# SuCOELora.net
KiCad netlist of a schematic drawn in Altium Designer
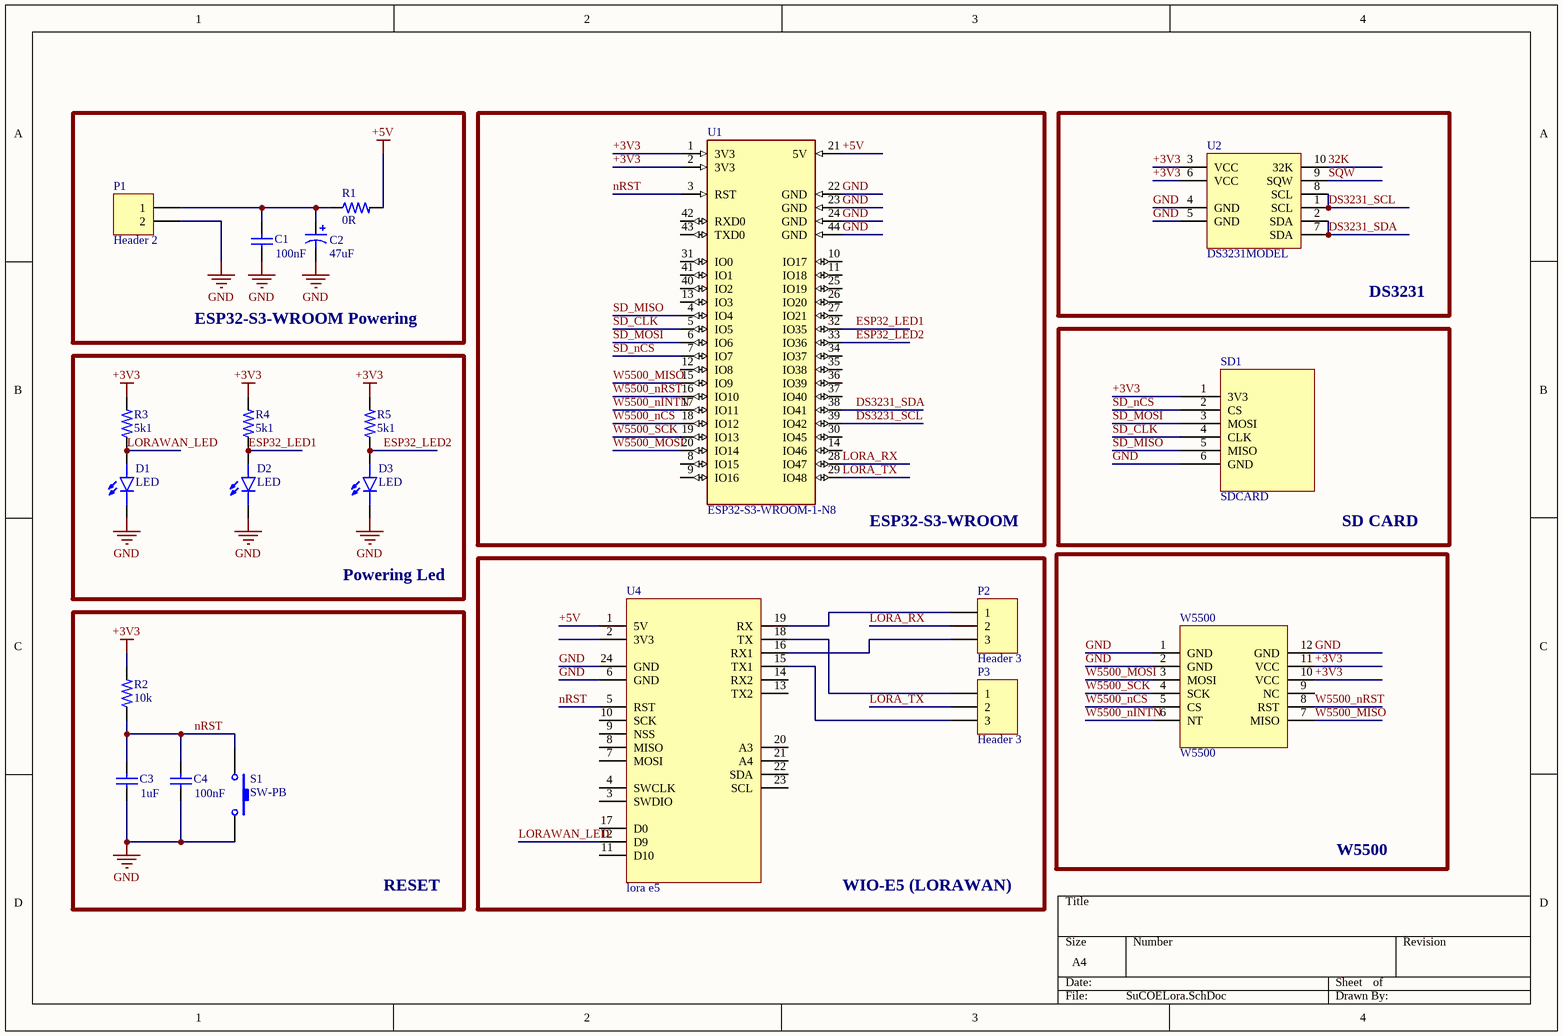
[diagram p0: SuCOELora.SchDoc]

(export (version "E")
  (design (tool "Eeschema 10.0.6"))
  (components
    (comp (ref "C1")
      (value "100nF")
      (footprint "CC0805")
      (description "Capacitor")
      (fields (field (name "Comment") "0805-50V-100nF±1%") (field (name "PUBLISHER") "Altium Limited"))
      (libsource (lib "Miscellaneous Devices") (part "Cap"))
    )
    (comp (ref "C2")
      (value "47uF")
      (footprint "SMD-EC-F4")
      (description "Polarized Capacitor (Radial)")
      (fields (field (name "Comment") "SMD-25V-47uF") (field (name "PUBLISHER") "Altium Limited"))
      (libsource (lib "Miscellaneous Devices") (part "Cap Pol1"))
    )
    (comp (ref "C3")
      (value "1uF")
      (footprint "CC0805")
      (description "Capacitor")
      (fields (field (name "Comment") "0805-50V-1uF±1%") (field (name "PUBLISHER") "Altium Limited"))
      (libsource (lib "Miscellaneous Devices") (part "Cap"))
    )
    (comp (ref "C4")
      (value "100nF")
      (footprint "CC0805")
      (description "Capacitor")
      (fields (field (name "Comment") "0805-50V-100nF±1%") (field (name "PUBLISHER") "Altium Limited"))
      (libsource (lib "Miscellaneous Devices") (part "Cap"))
    )
    (comp (ref "D1")
      (value "LED")
      (footprint "LED-R3")
      (description "LED Uni-Color Red 2-Pin Chip 0805 T/R")
      (fields (field (name "MP") "597-3305-607F"))
      (libsource (lib "Integrated_Library") (part "597-3305-607F"))
    )
    (comp (ref "D2")
      (value "LED")
      (footprint "LED-R3")
      (description "LED Uni-Color Red 2-Pin Chip 0805 T/R")
      (fields (field (name "MP") "597-3305-607F"))
      (libsource (lib "Integrated_Library") (part "597-3305-607F"))
    )
    (comp (ref "D3")
      (value "LED")
      (footprint "LED-R3")
      (description "LED Uni-Color Red 2-Pin Chip 0805 T/R")
      (fields (field (name "MP") "597-3305-607F"))
      (libsource (lib "Integrated_Library") (part "597-3305-607F"))
    )
    (comp (ref "P1")
      (value "Header 2")
      (footprint "2EDJKM3.81-2P")
      (description "Header, 2-Pin")
      (fields (field (name "PUBLISHER") "Altium Limited"))
      (libsource (lib "Miscellaneous Connectors") (part "Header 2"))
    )
    (comp (ref "P2")
      (value "Header 3")
      (footprint "HDR1X3")
      (description "Header, 3-Pin")
      (fields (field (name "PUBLISHER") "Altium Limited"))
      (libsource (lib "Miscellaneous Connectors") (part "Header 3"))
    )
    (comp (ref "P3")
      (value "Header 3")
      (footprint "HDR1X3")
      (description "Header, 3-Pin")
      (fields (field (name "PUBLISHER") "Altium Limited"))
      (libsource (lib "Miscellaneous Connectors") (part "Header 3"))
    )
    (comp (ref "R1")
      (value "0R")
      (footprint "0805")
      (description "SMD Chip Resistor, Jumper, 0 ohm, 100 mW, 0402 [1005 Metric], Thick Film, General Purpose")
      (fields
        (field (name "MANUFACTURER") "Panasonic")
        (field (name "MANUFACTURER PART NUMBER") "ERJ-2GE0R00X")
      )
      (libsource (lib "Integrated_Library") (part "0402 SMD Resistor"))
    )
    (comp (ref "R2")
      (value "10k")
      (footprint "0805")
      (description "Res Thick Film 0402 10K Ohm 5% 0.125W(1/8W) ±200ppm/C Pad SMD T/R")
      (fields
        (field (name "MANUFACTURER") "Yageo")
        (field (name "MANUFACTURER PART NUMBER") "RC0402JR-7W10KL")
      )
      (libsource (lib "Integrated_Library") (part "0402 SMD Resistor"))
    )
    (comp (ref "R3")
      (value "5k1")
      (footprint "0805")
      (description "General Purpose Chip Resistor Thick Film 0402 5.1kOhm 1% Paper T/R")
      (fields
        (field (name "MANUFACTURER") "Yageo")
        (field (name "MANUFACTURER PART NUMBER") "RC0402FR-7W5K1L")
      )
      (libsource (lib "Integrated_Library") (part "0402 SMD Resistor"))
    )
    (comp (ref "R4")
      (value "5k1")
      (footprint "0805")
      (description "General Purpose Chip Resistor Thick Film 0402 5.1kOhm 1% Paper T/R")
      (fields
        (field (name "MANUFACTURER") "Yageo")
        (field (name "MANUFACTURER PART NUMBER") "RC0402FR-7W5K1L")
      )
      (libsource (lib "Integrated_Library") (part "0402 SMD Resistor"))
    )
    (comp (ref "R5")
      (value "5k1")
      (footprint "0805")
      (description "General Purpose Chip Resistor Thick Film 0402 5.1kOhm 1% Paper T/R")
      (fields
        (field (name "MANUFACTURER") "Yageo")
        (field (name "MANUFACTURER PART NUMBER") "RC0402FR-7W5K1L")
      )
      (libsource (lib "Integrated_Library") (part "0402 SMD Resistor"))
    )
    (comp (ref "S1")
      (value "SW-PB")
      (footprint "KEY-4P")
      (description "Switch")
      (fields (field (name "PUBLISHER") "Altium Limited"))
      (libsource (lib "Miscellaneous Devices") (part "SW-PB"))
    )
    (comp (ref "SD1") (value "SDCARD") (footprint "SDCARD") (libsource (lib "PCB_Project") (part "SDCARD")))
    (comp (ref "U1")
      (value "ESP32-S3-WROOM-1-N8")
      (footprint "ESP32-S3")
      (fields (field (name "MF") "{'manufacturer': u'Espressif Systems'}"))
      (libsource (lib "PCB_Project") (part "ESP32-S3-WROOM-1-N8"))
    )
    (comp (ref "U2")
      (value "DS3231MODEL")
      (footprint "DS3231")
      (libsource (lib "PCB_Project") (part "DS3231MODEL"))
    )
    (comp (ref "U4")
      (value "lora e5")
      (footprint "USB2.0-TYPE-C")
      (libsource (lib "SuCOELora") (part "lora e5"))
    )
    (comp (ref "W5500") (value "W5500") (footprint "W5500") (libsource (lib "PCB_Project") (part "W5500")))
  )
  (nets
    (net (code "1") (name "+3V3") (class "Default")
      (node (ref "R2") (pin "2") (pinfunction "2_2") (pintype "passive"))
      (node (ref "R3") (pin "2") (pinfunction "2_2") (pintype "passive"))
      (node (ref "R4") (pin "2") (pinfunction "2_2") (pintype "passive"))
      (node (ref "R5") (pin "2") (pinfunction "2_2") (pintype "passive"))
      (node (ref "SD1") (pin "1") (pinfunction "3V3_1") (pintype "passive"))
      (node (ref "U1") (pin "1") (pinfunction "3V3_1") (pintype "input"))
      (node (ref "U1") (pin "2") (pinfunction "3V3_2") (pintype "input"))
      (node (ref "U2") (pin "3") (pinfunction "VCC_3") (pintype "passive"))
      (node (ref "U2") (pin "6") (pinfunction "VCC_6") (pintype "passive"))
      (node (ref "W5500") (pin "10") (pinfunction "VCC_10") (pintype "passive"))
      (node (ref "W5500") (pin "11") (pinfunction "VCC_11") (pintype "passive"))
    )
    (net (code "2") (name "+5V") (class "Default")
      (node (ref "R1") (pin "2") (pinfunction "2_2") (pintype "passive"))
      (node (ref "U1") (pin "21") (pinfunction "5V_21") (pintype "input"))
      (node (ref "U4") (pin "1") (pinfunction "5V_1") (pintype "passive"))
    )
    (net (code "3") (name "/32K") (class "Default")
      (node (ref "U2") (pin "10") (pinfunction "32K_10") (pintype "passive"))
    )
    (net (code "4") (name "/DS3231_SCL") (class "Default")
      (node (ref "U1") (pin "39") (pinfunction "IO42_39") (pintype "bidirectional"))
      (node (ref "U2") (pin "1") (pinfunction "SCL_1") (pintype "passive"))
      (node (ref "U2") (pin "8") (pinfunction "SCL_8") (pintype "passive"))
    )
    (net (code "5") (name "/DS3231_SDA") (class "Default")
      (node (ref "U1") (pin "38") (pinfunction "IO41_38") (pintype "bidirectional"))
      (node (ref "U2") (pin "2") (pinfunction "SDA_2") (pintype "passive"))
      (node (ref "U2") (pin "7") (pinfunction "SDA_7") (pintype "passive"))
    )
    (net (code "6") (name "/ESP32_LED1") (class "Default")
      (node (ref "D2") (pin "1") (pinfunction "A_1") (pintype "passive"))
      (node (ref "R4") (pin "1") (pinfunction "1_1") (pintype "passive"))
      (node (ref "U1") (pin "32") (pinfunction "IO35_32") (pintype "bidirectional"))
    )
    (net (code "7") (name "/ESP32_LED2") (class "Default")
      (node (ref "D3") (pin "1") (pinfunction "A_1") (pintype "passive"))
      (node (ref "R5") (pin "1") (pinfunction "1_1") (pintype "passive"))
      (node (ref "U1") (pin "33") (pinfunction "IO36_33") (pintype "bidirectional"))
    )
    (net (code "8") (name "/LORAWAN_LED") (class "Default")
      (node (ref "D1") (pin "1") (pinfunction "A_1") (pintype "passive"))
      (node (ref "R3") (pin "1") (pinfunction "1_1") (pintype "passive"))
      (node (ref "U4") (pin "12") (pinfunction "D9_12") (pintype "passive"))
    )
    (net (code "9") (name "/LORA_RX") (class "Default")
      (node (ref "P2") (pin "2") (pinfunction "2_2") (pintype "passive"))
      (node (ref "U1") (pin "28") (pinfunction "IO47_28") (pintype "bidirectional"))
    )
    (net (code "10") (name "/LORA_TX") (class "Default")
      (node (ref "P3") (pin "2") (pinfunction "2_2") (pintype "passive"))
      (node (ref "U1") (pin "29") (pinfunction "IO48_29") (pintype "bidirectional"))
    )
    (net (code "11") (name "/SD_CLK") (class "Default")
      (node (ref "SD1") (pin "4") (pinfunction "CLK_4") (pintype "passive"))
      (node (ref "U1") (pin "5") (pinfunction "IO5_5") (pintype "bidirectional"))
    )
    (net (code "12") (name "/SD_MISO") (class "Default")
      (node (ref "SD1") (pin "5") (pinfunction "MISO_5") (pintype "passive"))
      (node (ref "U1") (pin "4") (pinfunction "IO4_4") (pintype "bidirectional"))
    )
    (net (code "13") (name "/SD_MOSI") (class "Default")
      (node (ref "SD1") (pin "3") (pinfunction "MOSI_3") (pintype "passive"))
      (node (ref "U1") (pin "6") (pinfunction "IO6_6") (pintype "bidirectional"))
    )
    (net (code "14") (name "/SD_nCS") (class "Default")
      (node (ref "SD1") (pin "2") (pinfunction "CS_2") (pintype "passive"))
      (node (ref "U1") (pin "7") (pinfunction "IO7_7") (pintype "bidirectional"))
    )
    (net (code "15") (name "/SQW") (class "Default")
      (node (ref "U2") (pin "9") (pinfunction "SQW_9") (pintype "passive"))
    )
    (net (code "16") (name "/W5500_MISO") (class "Default")
      (node (ref "U1") (pin "15") (pinfunction "IO9_15") (pintype "bidirectional"))
      (node (ref "W5500") (pin "7") (pinfunction "MISO_7") (pintype "passive"))
    )
    (net (code "17") (name "/W5500_MOSI") (class "Default")
      (node (ref "U1") (pin "20") (pinfunction "IO14_20") (pintype "bidirectional"))
      (node (ref "W5500") (pin "3") (pinfunction "MOSI_3") (pintype "passive"))
    )
    (net (code "18") (name "/W5500_SCK") (class "Default")
      (node (ref "U1") (pin "19") (pinfunction "IO13_19") (pintype "bidirectional"))
      (node (ref "W5500") (pin "4") (pinfunction "SCK_4") (pintype "passive"))
    )
    (net (code "19") (name "/W5500_nCS") (class "Default")
      (node (ref "U1") (pin "18") (pinfunction "IO12_18") (pintype "bidirectional"))
      (node (ref "W5500") (pin "5") (pinfunction "CS_5") (pintype "passive"))
    )
    (net (code "20") (name "/W5500_nINTN") (class "Default")
      (node (ref "U1") (pin "17") (pinfunction "IO11_17") (pintype "bidirectional"))
      (node (ref "W5500") (pin "6") (pinfunction "NT_6") (pintype "passive"))
    )
    (net (code "21") (name "/W5500_nRST") (class "Default")
      (node (ref "U1") (pin "16") (pinfunction "IO10_16") (pintype "bidirectional"))
      (node (ref "W5500") (pin "8") (pinfunction "RST_8") (pintype "passive"))
    )
    (net (code "22") (name "/nRST") (class "Default")
      (node (ref "C3") (pin "2") (pinfunction "2_2") (pintype "passive"))
      (node (ref "C4") (pin "2") (pinfunction "2_2") (pintype "passive"))
      (node (ref "R2") (pin "1") (pinfunction "1_1") (pintype "passive"))
      (node (ref "S1") (pin "1") (pinfunction "1_1") (pintype "passive"))
      (node (ref "U1") (pin "3") (pinfunction "RST_3") (pintype "input"))
      (node (ref "U4") (pin "5") (pinfunction "RST_5") (pintype "passive"))
    )
    (net (code "23") (name "GND") (class "Default")
      (node (ref "C1") (pin "1") (pinfunction "1_1") (pintype "passive"))
      (node (ref "C2") (pin "2") (pinfunction "2_2") (pintype "passive"))
      (node (ref "C3") (pin "1") (pinfunction "1_1") (pintype "passive"))
      (node (ref "C4") (pin "1") (pinfunction "1_1") (pintype "passive"))
      (node (ref "D1") (pin "2") (pinfunction "C_2") (pintype "passive"))
      (node (ref "D2") (pin "2") (pinfunction "C_2") (pintype "passive"))
      (node (ref "D3") (pin "2") (pinfunction "C_2") (pintype "passive"))
      (node (ref "P1") (pin "2") (pinfunction "2_2") (pintype "passive"))
      (node (ref "S1") (pin "2") (pinfunction "2_2") (pintype "passive"))
      (node (ref "SD1") (pin "6") (pinfunction "GND_6") (pintype "passive"))
      (node (ref "U1") (pin "22") (pinfunction "GND_22") (pintype "input"))
      (node (ref "U1") (pin "23") (pinfunction "GND_23") (pintype "input"))
      (node (ref "U1") (pin "24") (pinfunction "GND_24") (pintype "input"))
      (node (ref "U1") (pin "44") (pinfunction "GND_44") (pintype "input"))
      (node (ref "U2") (pin "4") (pinfunction "GND_4") (pintype "passive"))
      (node (ref "U2") (pin "5") (pinfunction "GND_5") (pintype "passive"))
      (node (ref "U4") (pin "24") (pinfunction "GND_24") (pintype "passive"))
      (node (ref "U4") (pin "6") (pinfunction "GND_6") (pintype "passive"))
      (node (ref "W5500") (pin "1") (pinfunction "GND_1") (pintype "passive"))
      (node (ref "W5500") (pin "12") (pinfunction "GND_12") (pintype "passive"))
      (node (ref "W5500") (pin "2") (pinfunction "GND_2") (pintype "passive"))
    )
    (net (code "24") (name "Net-(C1-Pad2)") (class "Default")
      (node (ref "C1") (pin "2") (pinfunction "2_2") (pintype "passive"))
      (node (ref "C2") (pin "1") (pinfunction "1_1") (pintype "passive"))
      (node (ref "P1") (pin "1") (pinfunction "1_1") (pintype "passive"))
      (node (ref "R1") (pin "1") (pinfunction "1_1") (pintype "passive"))
    )
    (net (code "25") (name "Net-(U4-RX)") (class "Default")
      (node (ref "P2") (pin "1") (pinfunction "1_1") (pintype "passive"))
      (node (ref "U4") (pin "19") (pinfunction "RX_19") (pintype "passive"))
    )
    (net (code "26") (name "Net-(U4-RX1)") (class "Default")
      (node (ref "P2") (pin "3") (pinfunction "3_3") (pintype "passive"))
      (node (ref "U4") (pin "16") (pinfunction "RX1_16") (pintype "passive"))
    )
    (net (code "27") (name "Net-(U4-TX)") (class "Default")
      (node (ref "P3") (pin "1") (pinfunction "1_1") (pintype "passive"))
      (node (ref "U4") (pin "18") (pinfunction "TX_18") (pintype "passive"))
    )
    (net (code "28") (name "Net-(U4-TX1)") (class "Default")
      (node (ref "P3") (pin "3") (pinfunction "3_3") (pintype "passive"))
      (node (ref "U4") (pin "15") (pinfunction "TX1_15") (pintype "passive"))
    )
    (net (code "29") (name "unconnected-(U1-IO0-Pad31)") (class "Default")
      (node (ref "U1") (pin "31") (pinfunction "IO0_31") (pintype "bidirectional"))
    )
    (net (code "30") (name "unconnected-(U1-IO1-Pad41)") (class "Default")
      (node (ref "U1") (pin "41") (pinfunction "IO1_41") (pintype "bidirectional"))
    )
    (net (code "31") (name "unconnected-(U1-IO2-Pad40)") (class "Default")
      (node (ref "U1") (pin "40") (pinfunction "IO2_40") (pintype "bidirectional"))
    )
    (net (code "32") (name "unconnected-(U1-IO3-Pad13)") (class "Default")
      (node (ref "U1") (pin "13") (pinfunction "IO3_13") (pintype "bidirectional"))
    )
    (net (code "33") (name "unconnected-(U1-IO8-Pad12)") (class "Default")
      (node (ref "U1") (pin "12") (pinfunction "IO8_12") (pintype "bidirectional"))
    )
    (net (code "34") (name "unconnected-(U1-IO15-Pad8)") (class "Default")
      (node (ref "U1") (pin "8") (pinfunction "IO15_8") (pintype "bidirectional"))
    )
    (net (code "35") (name "unconnected-(U1-IO16-Pad9)") (class "Default")
      (node (ref "U1") (pin "9") (pinfunction "IO16_9") (pintype "bidirectional"))
    )
    (net (code "36") (name "unconnected-(U1-IO17-Pad10)") (class "Default")
      (node (ref "U1") (pin "10") (pinfunction "IO17_10") (pintype "bidirectional"))
    )
    (net (code "37") (name "unconnected-(U1-IO18-Pad11)") (class "Default")
      (node (ref "U1") (pin "11") (pinfunction "IO18_11") (pintype "bidirectional"))
    )
    (net (code "38") (name "unconnected-(U1-IO19-Pad25)") (class "Default")
      (node (ref "U1") (pin "25") (pinfunction "IO19_25") (pintype "bidirectional"))
    )
    (net (code "39") (name "unconnected-(U1-IO20-Pad26)") (class "Default")
      (node (ref "U1") (pin "26") (pinfunction "IO20_26") (pintype "bidirectional"))
    )
    (net (code "40") (name "unconnected-(U1-IO21-Pad27)") (class "Default")
      (node (ref "U1") (pin "27") (pinfunction "IO21_27") (pintype "bidirectional"))
    )
    (net (code "41") (name "unconnected-(U1-IO37-Pad34)") (class "Default")
      (node (ref "U1") (pin "34") (pinfunction "IO37_34") (pintype "bidirectional"))
    )
    (net (code "42") (name "unconnected-(U1-IO38-Pad35)") (class "Default")
      (node (ref "U1") (pin "35") (pinfunction "IO38_35") (pintype "bidirectional"))
    )
    (net (code "43") (name "unconnected-(U1-IO39-Pad36)") (class "Default")
      (node (ref "U1") (pin "36") (pinfunction "IO39_36") (pintype "bidirectional"))
    )
    (net (code "44") (name "unconnected-(U1-IO40-Pad37)") (class "Default")
      (node (ref "U1") (pin "37") (pinfunction "IO40_37") (pintype "bidirectional"))
    )
    (net (code "45") (name "unconnected-(U1-IO45-Pad30)") (class "Default")
      (node (ref "U1") (pin "30") (pinfunction "IO45_30") (pintype "bidirectional"))
    )
    (net (code "46") (name "unconnected-(U1-IO46-Pad14)") (class "Default")
      (node (ref "U1") (pin "14") (pinfunction "IO46_14") (pintype "bidirectional"))
    )
    (net (code "47") (name "unconnected-(U1-RXD0-Pad42)") (class "Default")
      (node (ref "U1") (pin "42") (pinfunction "RXD0_42") (pintype "bidirectional"))
    )
    (net (code "48") (name "unconnected-(U1-TXD0-Pad43)") (class "Default")
      (node (ref "U1") (pin "43") (pinfunction "TXD0_43") (pintype "bidirectional"))
    )
    (net (code "49") (name "unconnected-(U4-3V3-Pad2)") (class "Default")
      (node (ref "U4") (pin "2") (pinfunction "3V3_2") (pintype "passive"))
    )
    (net (code "50") (name "unconnected-(U4-A3-Pad20)") (class "Default")
      (node (ref "U4") (pin "20") (pinfunction "A3_20") (pintype "passive"))
    )
    (net (code "51") (name "unconnected-(U4-A4-Pad21)") (class "Default")
      (node (ref "U4") (pin "21") (pinfunction "A4_21") (pintype "passive"))
    )
    (net (code "52") (name "unconnected-(U4-D0-Pad17)") (class "Default")
      (node (ref "U4") (pin "17") (pinfunction "D0_17") (pintype "passive"))
    )
    (net (code "53") (name "unconnected-(U4-D10-Pad11)") (class "Default")
      (node (ref "U4") (pin "11") (pinfunction "D10_11") (pintype "passive"))
    )
    (net (code "54") (name "unconnected-(U4-MISO-Pad8)") (class "Default")
      (node (ref "U4") (pin "8") (pinfunction "MISO_8") (pintype "passive"))
    )
    (net (code "55") (name "unconnected-(U4-MOSI-Pad7)") (class "Default")
      (node (ref "U4") (pin "7") (pinfunction "MOSI_7") (pintype "passive"))
    )
    (net (code "56") (name "unconnected-(U4-NSS-Pad9)") (class "Default")
      (node (ref "U4") (pin "9") (pinfunction "NSS_9") (pintype "passive"))
    )
    (net (code "57") (name "unconnected-(U4-RX2-Pad14)") (class "Default")
      (node (ref "U4") (pin "14") (pinfunction "RX2_14") (pintype "passive"))
    )
    (net (code "58") (name "unconnected-(U4-SCK-Pad10)") (class "Default")
      (node (ref "U4") (pin "10") (pinfunction "SCK_10") (pintype "passive"))
    )
    (net (code "59") (name "unconnected-(U4-SCL-Pad23)") (class "Default")
      (node (ref "U4") (pin "23") (pinfunction "SCL_23") (pintype "passive"))
    )
    (net (code "60") (name "unconnected-(U4-SDA-Pad22)") (class "Default")
      (node (ref "U4") (pin "22") (pinfunction "SDA_22") (pintype "passive"))
    )
    (net (code "61") (name "unconnected-(U4-SWCLK-Pad4)") (class "Default")
      (node (ref "U4") (pin "4") (pinfunction "SWCLK_4") (pintype "passive"))
    )
    (net (code "62") (name "unconnected-(U4-SWDIO-Pad3)") (class "Default")
      (node (ref "U4") (pin "3") (pinfunction "SWDIO_3") (pintype "passive"))
    )
    (net (code "63") (name "unconnected-(U4-TX2-Pad13)") (class "Default")
      (node (ref "U4") (pin "13") (pinfunction "TX2_13") (pintype "passive"))
    )
    (net (code "64") (name "unconnected-(W5500-NC-Pad9)") (class "Default")
      (node (ref "W5500") (pin "9") (pinfunction "NC_9") (pintype "passive"))
    )
  )
)
